# indicator.net
KiCad netlist of a schematic drawn in Altium Designer
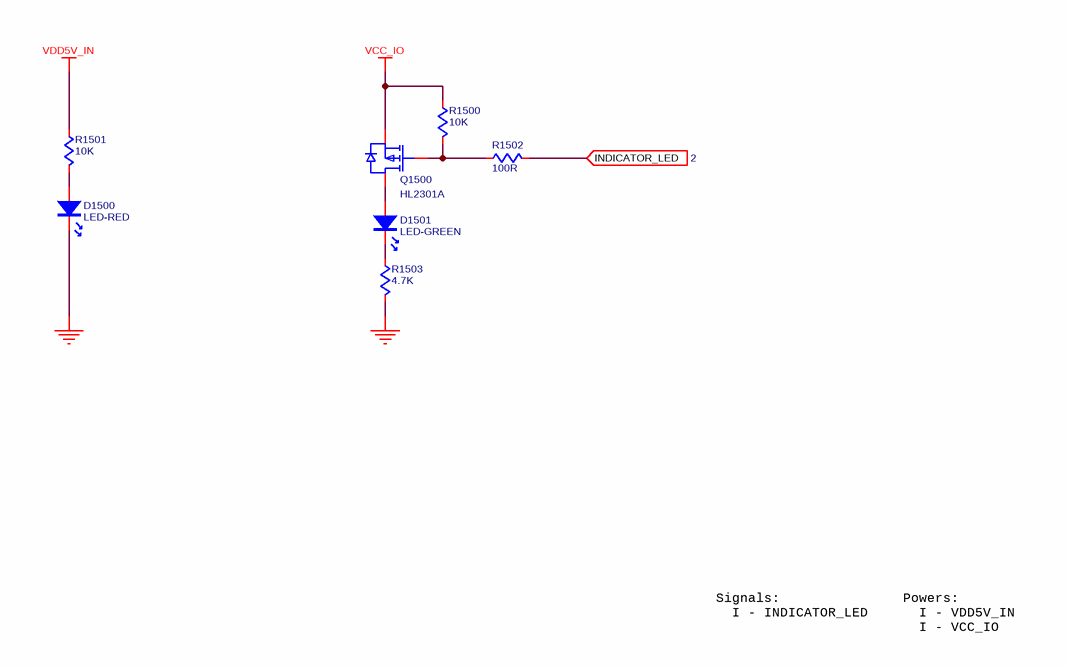
[diagram p0: indicator.schdoc]

(export (version "E")
  (design (tool "Eeschema 10.0.6"))
  (components
    (comp (ref "D1500") (value "LED-RED") (footprint "mw:LED0603") (libsource (lib "mw") (part "LED")))
    (comp (ref "D1501") (value "LED-GREEN") (footprint "mw:LED0603") (libsource (lib "mw") (part "LED")))
    (comp (ref "Q1500")
      (value "HL2301A")
      (footprint "mw:HL2301A")
      (description "PMOS")
      (libsource (lib "mw") (part "HL2301A"))
    )
    (comp (ref "R1500")
      (value "10K")
      (footprint "mw:R0402")
      (fields (field (name "Comment") "R"))
      (libsource (lib "mw") (part "R"))
    )
    (comp (ref "R1501")
      (value "10K")
      (footprint "mw:R0402")
      (fields (field (name "Comment") "R"))
      (libsource (lib "mw") (part "R"))
    )
    (comp (ref "R1502")
      (value "100R")
      (footprint "mw:R0402")
      (fields (field (name "Comment") "R"))
      (libsource (lib "mw") (part "R"))
    )
    (comp (ref "R1503")
      (value "4.7K")
      (footprint "mw:R0402")
      (fields (field (name "Comment") "R"))
      (libsource (lib "mw") (part "R"))
    )
  )
  (nets
    (net (code "1") (name "/INDICATOR_LED") (class "Default")
      (node (ref "R1502") (pin "1") (pinfunction "1_1") (pintype "passive"))
    )
    (net (code "2") (name "GND") (class "Default")
      (node (ref "D1500") (pin "1") (pinfunction "1_1") (pintype "passive"))
      (node (ref "R1503") (pin "1") (pinfunction "1_1") (pintype "passive"))
    )
    (net (code "3") (name "Net-(D1500-Pad2)") (class "Default")
      (node (ref "D1500") (pin "2") (pinfunction "2_2") (pintype "passive"))
      (node (ref "R1501") (pin "1") (pinfunction "1_1") (pintype "passive"))
    )
    (net (code "4") (name "Net-(D1501-Pad1)") (class "Default")
      (node (ref "D1501") (pin "1") (pinfunction "1_1") (pintype "passive"))
      (node (ref "R1503") (pin "2") (pinfunction "2_2") (pintype "passive"))
    )
    (net (code "5") (name "Net-(D1501-Pad2)") (class "Default")
      (node (ref "D1501") (pin "2") (pinfunction "2_2") (pintype "passive"))
      (node (ref "Q1500") (pin "D") (pinfunction "D_D") (pintype "passive"))
    )
    (net (code "6") (name "Net-(Q1500-PadG)") (class "Default")
      (node (ref "Q1500") (pin "G") (pinfunction "G_G") (pintype "passive"))
      (node (ref "R1500") (pin "1") (pinfunction "1_1") (pintype "passive"))
      (node (ref "R1502") (pin "2") (pinfunction "2_2") (pintype "passive"))
    )
    (net (code "7") (name "VCC_IO") (class "Default")
      (node (ref "Q1500") (pin "S") (pinfunction "S_S") (pintype "passive"))
      (node (ref "R1500") (pin "2") (pinfunction "2_2") (pintype "passive"))
    )
    (net (code "8") (name "VDD5V_IN") (class "Default")
      (node (ref "R1501") (pin "2") (pinfunction "2_2") (pintype "passive"))
    )
  )
)
